# cs301_Team01_Schematic.net
KiCad netlist of a schematic drawn in Altium Designer
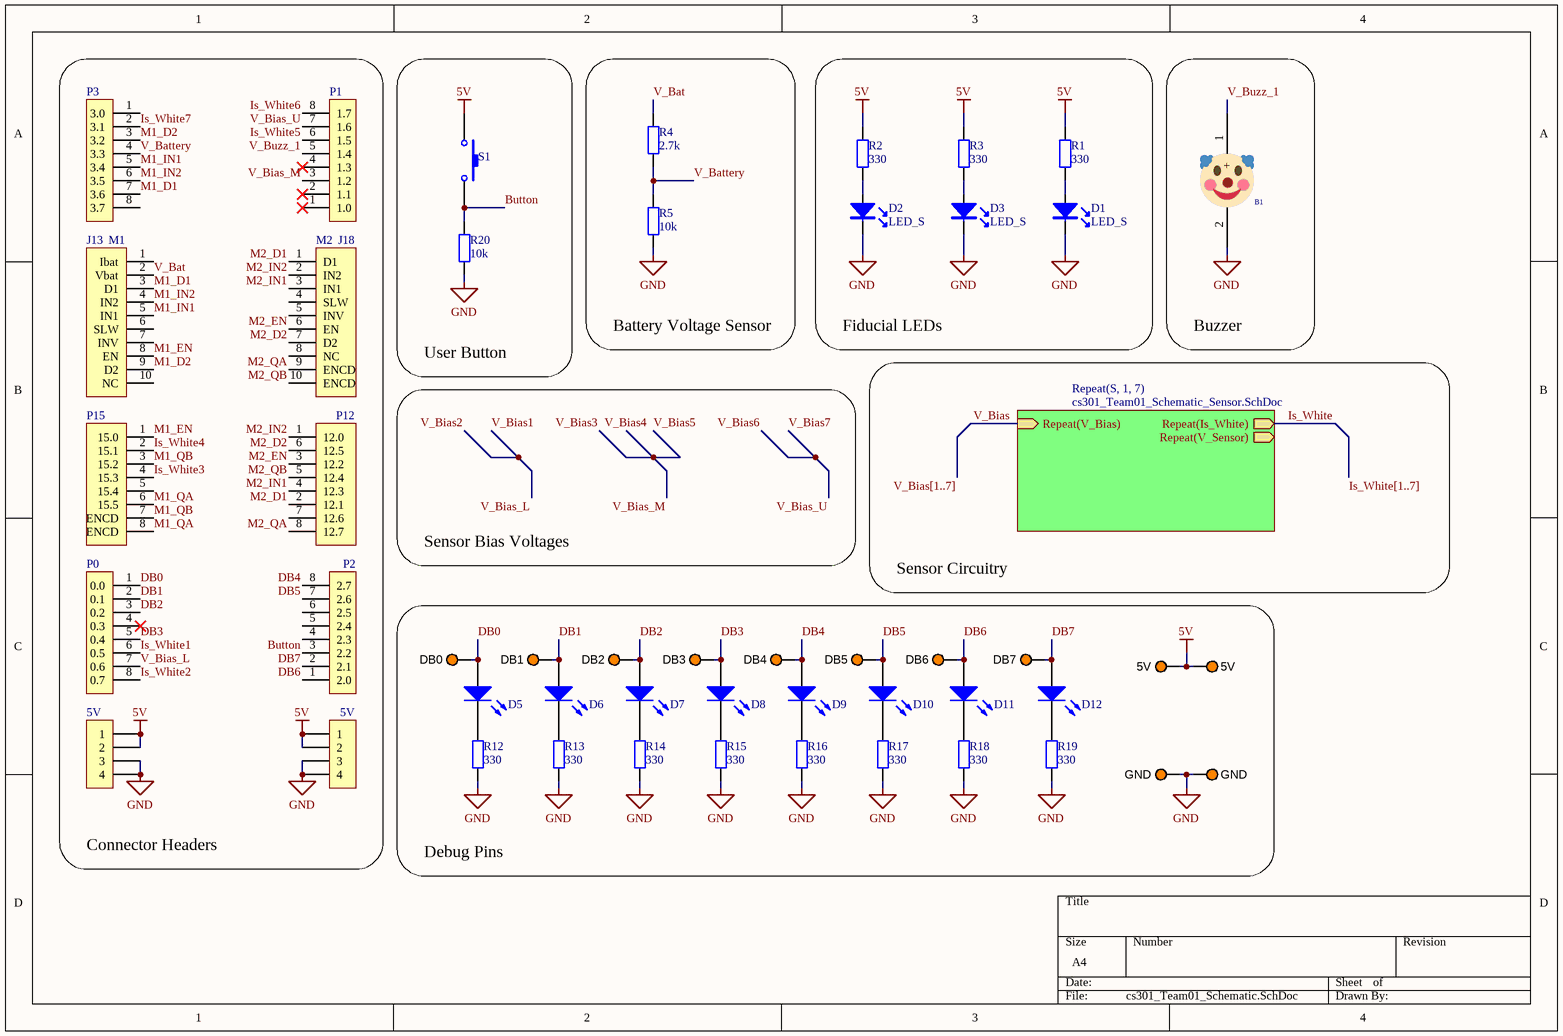
[diagram p0: cs301_Team01_Schematic.SchDoc]

(export (version "E")
  (design (tool "Eeschema 10.0.6"))
  (components
    (comp (ref "+5V")
      (value "5V")
      (footprint "IDC4")
      (description "Connector")
      (libsource (lib "Miscellaneous Devices") (part "CON4"))
    )
    (comp (ref "5V")
      (value "5V")
      (footprint "IDC4")
      (description "Connector")
      (libsource (lib "") (part "CON4_1"))
    )
    (comp (ref "5V_1")
      (value "5V")
      (footprint "TP_TH")
      (description "Test Point, Orange, 1-Pin THD, RoHS")
      (libsource (lib "EE209_Library") (part "TestPoint"))
    )
    (comp (ref "5V_2")
      (value "5V")
      (footprint "TP_TH")
      (description "Test Point, Orange, 1-Pin THD, RoHS")
      (libsource (lib "EE209_Library") (part "TestPoint"))
    )
    (comp (ref "B1") (value "clown") (footprint "Buzzer") (libsource (lib "buzzer") (part "Buzzer")))
    (comp (ref "D1") (value "LED_S") (footprint "LED0.1/5MM") (libsource (lib "COMSYS301_2013") (part "LED")))
    (comp (ref "D2") (value "LED_S") (footprint "LED0.1/5MM") (libsource (lib "COMSYS301_2013") (part "LED")))
    (comp (ref "D3") (value "LED_S") (footprint "LED0.1/5MM") (libsource (lib "COMSYS301_2013") (part "LED")))
    (comp (ref "D5")
      (value "0")
      (footprint "0805 LED")
      (description "SMT LED 0805 size")
      (fields
        (field (name "MANUFACTURER") "Lite-On Inc.")
        (field (name "MANUFACTURER PART NUMBER") "LTST-C170KGKT")
      )
      (libsource (lib "EE209_Library") (part "LED_SMT_0805"))
    )
    (comp (ref "D6")
      (value "1")
      (footprint "0805 LED")
      (description "SMT LED 0805 size")
      (fields
        (field (name "MANUFACTURER") "Lite-On Inc.")
        (field (name "MANUFACTURER PART NUMBER") "LTST-C170KGKT")
      )
      (libsource (lib "EE209_Library") (part "LED_SMT_0805"))
    )
    (comp (ref "D7")
      (value "2")
      (footprint "0805 LED")
      (description "SMT LED 0805 size")
      (fields
        (field (name "MANUFACTURER") "Lite-On Inc.")
        (field (name "MANUFACTURER PART NUMBER") "LTST-C170KGKT")
      )
      (libsource (lib "EE209_Library") (part "LED_SMT_0805"))
    )
    (comp (ref "D8")
      (value "3")
      (footprint "0805 LED")
      (description "SMT LED 0805 size")
      (fields
        (field (name "MANUFACTURER") "Lite-On Inc.")
        (field (name "MANUFACTURER PART NUMBER") "LTST-C170KGKT")
      )
      (libsource (lib "EE209_Library") (part "LED_SMT_0805"))
    )
    (comp (ref "D9")
      (value "4")
      (footprint "0805 LED")
      (description "SMT LED 0805 size")
      (fields
        (field (name "MANUFACTURER") "Lite-On Inc.")
        (field (name "MANUFACTURER PART NUMBER") "LTST-C170KGKT")
      )
      (libsource (lib "EE209_Library") (part "LED_SMT_0805"))
    )
    (comp (ref "D10")
      (value "5")
      (footprint "0805 LED")
      (description "SMT LED 0805 size")
      (fields
        (field (name "MANUFACTURER") "Lite-On Inc.")
        (field (name "MANUFACTURER PART NUMBER") "LTST-C170KGKT")
      )
      (libsource (lib "EE209_Library") (part "LED_SMT_0805"))
    )
    (comp (ref "D11")
      (value "6")
      (footprint "0805 LED")
      (description "SMT LED 0805 size")
      (fields
        (field (name "MANUFACTURER") "Lite-On Inc.")
        (field (name "MANUFACTURER PART NUMBER") "LTST-C170KGKT")
      )
      (libsource (lib "EE209_Library") (part "LED_SMT_0805"))
    )
    (comp (ref "D12")
      (value "7")
      (footprint "0805 LED")
      (description "SMT LED 0805 size")
      (fields
        (field (name "MANUFACTURER") "Lite-On Inc.")
        (field (name "MANUFACTURER PART NUMBER") "LTST-C170KGKT")
      )
      (libsource (lib "EE209_Library") (part "LED_SMT_0805"))
    )
    (comp (ref "DB0")
      (value "5003")
      (footprint "TP_TH")
      (description "Test Point, Orange, 1-Pin THD, RoHS")
      (libsource (lib "EE209_Library") (part "TestPoint"))
    )
    (comp (ref "DB1")
      (value "5003")
      (footprint "TP_TH")
      (description "Test Point, Orange, 1-Pin THD, RoHS")
      (libsource (lib "EE209_Library") (part "TestPoint"))
    )
    (comp (ref "DB2")
      (value "5003")
      (footprint "TP_TH")
      (description "Test Point, Orange, 1-Pin THD, RoHS")
      (libsource (lib "EE209_Library") (part "TestPoint"))
    )
    (comp (ref "DB3")
      (value "5003")
      (footprint "TP_TH")
      (description "Test Point, Orange, 1-Pin THD, RoHS")
      (libsource (lib "EE209_Library") (part "TestPoint"))
    )
    (comp (ref "DB4")
      (value "5003")
      (footprint "TP_TH")
      (description "Test Point, Orange, 1-Pin THD, RoHS")
      (libsource (lib "EE209_Library") (part "TestPoint"))
    )
    (comp (ref "DB5")
      (value "5003")
      (footprint "TP_TH")
      (description "Test Point, Orange, 1-Pin THD, RoHS")
      (libsource (lib "EE209_Library") (part "TestPoint"))
    )
    (comp (ref "DB6")
      (value "5003")
      (footprint "TP_TH")
      (description "Test Point, Orange, 1-Pin THD, RoHS")
      (libsource (lib "EE209_Library") (part "TestPoint"))
    )
    (comp (ref "DB7")
      (value "5003")
      (footprint "TP_TH")
      (description "Test Point, Orange, 1-Pin THD, RoHS")
      (libsource (lib "EE209_Library") (part "TestPoint"))
    )
    (comp (ref "GND_1")
      (value "GND")
      (footprint "TP_TH")
      (description "Test Point, Orange, 1-Pin THD, RoHS")
      (libsource (lib "EE209_Library") (part "TestPoint"))
    )
    (comp (ref "GND_2")
      (value "GND")
      (footprint "TP_TH")
      (description "Test Point, Orange, 1-Pin THD, RoHS")
      (libsource (lib "EE209_Library") (part "TestPoint"))
    )
    (comp (ref "J13")
      (value "M1")
      (footprint "idc10")
      (description "Connector")
      (libsource (lib "Miscellaneous Devices") (part "CON10"))
    )
    (comp (ref "J18")
      (value "M2")
      (footprint "IDC10")
      (description "Connector")
      (libsource (lib "") (part "CON10_1"))
    )
    (comp (ref "P0")
      (value "P0")
      (footprint "idc8")
      (description "Connector")
      (libsource (lib "") (part "CON8_2"))
    )
    (comp (ref "P1")
      (value "P1")
      (footprint "idc8")
      (description "Connector")
      (libsource (lib "Miscellaneous Devices") (part "CON8"))
    )
    (comp (ref "P2")
      (value "P2")
      (footprint "idc8")
      (description "Connector")
      (libsource (lib "") (part "CON8_1"))
    )
    (comp (ref "P3")
      (value "P3")
      (footprint "idc8")
      (description "Connector")
      (libsource (lib "") (part "CON8_2"))
    )
    (comp (ref "P12")
      (value "P12")
      (footprint "idc8")
      (description "Connector")
      (libsource (lib "") (part "CON8_1_1"))
    )
    (comp (ref "P15")
      (value "P15")
      (footprint "idc8")
      (description "Connector")
      (libsource (lib "Miscellaneous Devices") (part "CON8_1"))
    )
    (comp (ref "R1")
      (value "330")
      (footprint "0805 RES")
      (description "0805 resistor")
      (fields (field (name "PUBLISHER") "Altium Limited"))
      (libsource (lib "EE209_Library") (part "Res_SMT_0805"))
    )
    (comp (ref "R2")
      (value "330")
      (footprint "0805 RES")
      (description "0805 resistor")
      (fields (field (name "PUBLISHER") "Altium Limited"))
      (libsource (lib "EE209_Library") (part "Res_SMT_0805"))
    )
    (comp (ref "R3")
      (value "330")
      (footprint "0805 RES")
      (description "0805 resistor")
      (fields (field (name "PUBLISHER") "Altium Limited"))
      (libsource (lib "EE209_Library") (part "Res_SMT_0805"))
    )
    (comp (ref "R4")
      (value "2.7k")
      (footprint "0805 RES")
      (description "0805 resistor")
      (fields (field (name "PUBLISHER") "Altium Limited"))
      (libsource (lib "EE209_Library") (part "Res_SMT_0805"))
    )
    (comp (ref "R5")
      (value "10k")
      (footprint "0805 RES")
      (description "0805 resistor")
      (fields (field (name "PUBLISHER") "Altium Limited"))
      (libsource (lib "EE209_Library") (part "Res_SMT_0805"))
    )
    (comp (ref "R12")
      (value "330")
      (footprint "0805 RES")
      (description "0805 resistor")
      (fields (field (name "PUBLISHER") "Altium Limited"))
      (libsource (lib "EE209_Library") (part "Res_SMT_0805"))
    )
    (comp (ref "R13")
      (value "330")
      (footprint "0805 RES")
      (description "0805 resistor")
      (fields (field (name "PUBLISHER") "Altium Limited"))
      (libsource (lib "EE209_Library") (part "Res_SMT_0805"))
    )
    (comp (ref "R14")
      (value "330")
      (footprint "0805 RES")
      (description "0805 resistor")
      (fields (field (name "PUBLISHER") "Altium Limited"))
      (libsource (lib "EE209_Library") (part "Res_SMT_0805"))
    )
    (comp (ref "R15")
      (value "330")
      (footprint "0805 RES")
      (description "0805 resistor")
      (fields (field (name "PUBLISHER") "Altium Limited"))
      (libsource (lib "EE209_Library") (part "Res_SMT_0805"))
    )
    (comp (ref "R16")
      (value "330")
      (footprint "0805 RES")
      (description "0805 resistor")
      (fields (field (name "PUBLISHER") "Altium Limited"))
      (libsource (lib "EE209_Library") (part "Res_SMT_0805"))
    )
    (comp (ref "R17")
      (value "330")
      (footprint "0805 RES")
      (description "0805 resistor")
      (fields (field (name "PUBLISHER") "Altium Limited"))
      (libsource (lib "EE209_Library") (part "Res_SMT_0805"))
    )
    (comp (ref "R18")
      (value "330")
      (footprint "0805 RES")
      (description "0805 resistor")
      (fields (field (name "PUBLISHER") "Altium Limited"))
      (libsource (lib "EE209_Library") (part "Res_SMT_0805"))
    )
    (comp (ref "R19")
      (value "330")
      (footprint "0805 RES")
      (description "0805 resistor")
      (fields (field (name "PUBLISHER") "Altium Limited"))
      (libsource (lib "EE209_Library") (part "Res_SMT_0805"))
    )
    (comp (ref "R20")
      (value "10k")
      (footprint "0805 RES")
      (description "0805 resistor")
      (fields (field (name "PUBLISHER") "Altium Limited"))
      (libsource (lib "EE209_Library") (part "Res_SMT_0805"))
    )
    (comp (ref "S1")
      (value "PB switchTH_small")
      (footprint "ece-Sw-small")
      (description "Push Button Switch thru hole")
      (libsource (lib "ece components") (part "PB switchTH_small"))
    )
  )
  (nets
    (net (code "1") (name "/Button") (class "Default")
      (node (ref "P2") (pin "3") (pinfunction "2.2_3") (pintype "passive"))
      (node (ref "R20") (pin "2") (pinfunction "2_2") (pintype "passive"))
      (node (ref "S1") (pin "2") (pinfunction "2_2") (pintype "passive"))
    )
    (net (code "2") (name "/DB0") (class "Default")
      (node (ref "D5") (pin "1") (pinfunction "A_1") (pintype "passive"))
      (node (ref "DB0") (pin "1") (pinfunction "1_1") (pintype "passive"))
      (node (ref "P0") (pin "1") (pinfunction "3.0_1") (pintype "passive"))
    )
    (net (code "3") (name "/DB1") (class "Default")
      (node (ref "D6") (pin "1") (pinfunction "A_1") (pintype "passive"))
      (node (ref "DB1") (pin "1") (pinfunction "1_1") (pintype "passive"))
      (node (ref "P0") (pin "2") (pinfunction "3.1_2") (pintype "passive"))
    )
    (net (code "4") (name "/DB2") (class "Default")
      (node (ref "D7") (pin "1") (pinfunction "A_1") (pintype "passive"))
      (node (ref "DB2") (pin "1") (pinfunction "1_1") (pintype "passive"))
      (node (ref "P0") (pin "3") (pinfunction "3.2_3") (pintype "passive"))
    )
    (net (code "5") (name "/DB3") (class "Default")
      (node (ref "D8") (pin "1") (pinfunction "A_1") (pintype "passive"))
      (node (ref "DB3") (pin "1") (pinfunction "1_1") (pintype "passive"))
      (node (ref "P0") (pin "5") (pinfunction "3.4_5") (pintype "passive"))
    )
    (net (code "6") (name "/DB4") (class "Default")
      (node (ref "D9") (pin "1") (pinfunction "A_1") (pintype "passive"))
      (node (ref "DB4") (pin "1") (pinfunction "1_1") (pintype "passive"))
      (node (ref "P2") (pin "8") (pinfunction "2.7_8") (pintype "passive"))
    )
    (net (code "7") (name "/DB5") (class "Default")
      (node (ref "D10") (pin "1") (pinfunction "A_1") (pintype "passive"))
      (node (ref "DB5") (pin "1") (pinfunction "1_1") (pintype "passive"))
      (node (ref "P2") (pin "7") (pinfunction "2.6_7") (pintype "passive"))
    )
    (net (code "8") (name "/DB6") (class "Default")
      (node (ref "D11") (pin "1") (pinfunction "A_1") (pintype "passive"))
      (node (ref "DB6") (pin "1") (pinfunction "1_1") (pintype "passive"))
      (node (ref "P2") (pin "1") (pinfunction "2.0_1") (pintype "passive"))
    )
    (net (code "9") (name "/DB7") (class "Default")
      (node (ref "D12") (pin "1") (pinfunction "A_1") (pintype "passive"))
      (node (ref "DB7") (pin "1") (pinfunction "1_1") (pintype "passive"))
      (node (ref "P2") (pin "2") (pinfunction "2.1_2") (pintype "passive"))
    )
    (net (code "11") (name "/Is_White1") (class "Default")
      (node (ref "P0") (pin "6") (pinfunction "3.5_6") (pintype "passive"))
    )
    (net (code "12") (name "/Is_White2") (class "Default")
      (node (ref "P0") (pin "8") (pinfunction "3.7_8") (pintype "passive"))
    )
    (net (code "13") (name "/Is_White3") (class "Default")
      (node (ref "P15") (pin "4") (pinfunction "15.3_4") (pintype "passive"))
    )
    (net (code "14") (name "/Is_White4") (class "Default")
      (node (ref "P15") (pin "2") (pinfunction "15.1_2") (pintype "passive"))
    )
    (net (code "15") (name "/Is_White5") (class "Default")
      (node (ref "P1") (pin "6") (pinfunction "1.5_6") (pintype "passive"))
    )
    (net (code "16") (name "/Is_White6") (class "Default")
      (node (ref "P1") (pin "8") (pinfunction "1.7_8") (pintype "passive"))
    )
    (net (code "17") (name "/Is_White7") (class "Default")
      (node (ref "P3") (pin "2") (pinfunction "3.1_2") (pintype "passive"))
    )
    (net (code "19") (name "/M1_D1") (class "Default")
      (node (ref "J13") (pin "3") (pinfunction "D1_3") (pintype "passive"))
      (node (ref "P3") (pin "7") (pinfunction "3.6_7") (pintype "passive"))
    )
    (net (code "20") (name "/M1_D2") (class "Default")
      (node (ref "J13") (pin "9") (pinfunction "D2_9") (pintype "passive"))
      (node (ref "P3") (pin "3") (pinfunction "3.2_3") (pintype "passive"))
    )
    (net (code "21") (name "/M1_EN") (class "Default")
      (node (ref "J13") (pin "8") (pinfunction "EN_8") (pintype "passive"))
      (node (ref "P15") (pin "1") (pinfunction "15.0_1") (pintype "passive"))
    )
    (net (code "22") (name "/M1_IN1") (class "Default")
      (node (ref "J13") (pin "5") (pinfunction "IN1_5") (pintype "passive"))
      (node (ref "P3") (pin "5") (pinfunction "3.4_5") (pintype "passive"))
    )
    (net (code "23") (name "/M1_IN2") (class "Default")
      (node (ref "J13") (pin "4") (pinfunction "IN2_4") (pintype "passive"))
      (node (ref "P3") (pin "6") (pinfunction "3.5_6") (pintype "passive"))
    )
    (net (code "24") (name "/M1_QA") (class "Default")
      (node (ref "P15") (pin "6") (pinfunction "15.5_6") (pintype "passive"))
      (node (ref "P15") (pin "8") (pinfunction "ENCD_8") (pintype "passive"))
    )
    (net (code "25") (name "/M1_QB") (class "Default")
      (node (ref "P15") (pin "3") (pinfunction "15.2_3") (pintype "passive"))
      (node (ref "P15") (pin "7") (pinfunction "ENCD_7") (pintype "passive"))
    )
    (net (code "26") (name "/M2_D1") (class "Default")
      (node (ref "J18") (pin "1") (pinfunction "D1_1") (pintype "passive"))
      (node (ref "P12") (pin "2") (pinfunction "12.1_2") (pintype "passive"))
    )
    (net (code "27") (name "/M2_D2") (class "Default")
      (node (ref "J18") (pin "7") (pinfunction "D2_7") (pintype "passive"))
      (node (ref "P12") (pin "6") (pinfunction "12.5_6") (pintype "passive"))
    )
    (net (code "28") (name "/M2_EN") (class "Default")
      (node (ref "J18") (pin "6") (pinfunction "EN_6") (pintype "passive"))
      (node (ref "P12") (pin "3") (pinfunction "12.2_3") (pintype "passive"))
    )
    (net (code "29") (name "/M2_IN1") (class "Default")
      (node (ref "J18") (pin "3") (pinfunction "IN1_3") (pintype "passive"))
      (node (ref "P12") (pin "4") (pinfunction "12.3_4") (pintype "passive"))
    )
    (net (code "30") (name "/M2_IN2") (class "Default")
      (node (ref "J18") (pin "2") (pinfunction "IN2_2") (pintype "passive"))
      (node (ref "P12") (pin "1") (pinfunction "12.0_1") (pintype "passive"))
    )
    (net (code "31") (name "/M2_QA") (class "Default")
      (node (ref "J18") (pin "9") (pinfunction "ENCD_9") (pintype "passive"))
      (node (ref "P12") (pin "8") (pinfunction "12.7_8") (pintype "passive"))
    )
    (net (code "32") (name "/M2_QB") (class "Default")
      (node (ref "J18") (pin "10") (pinfunction "ENCD_10") (pintype "passive"))
      (node (ref "P12") (pin "5") (pinfunction "12.4_5") (pintype "passive"))
    )
    (net (code "34") (name "/V_Bat") (class "Default")
      (node (ref "J13") (pin "2") (pinfunction "Vbat_2") (pintype "passive"))
      (node (ref "R4") (pin "2") (pinfunction "2_2") (pintype "passive"))
    )
    (net (code "35") (name "/V_Battery") (class "Default")
      (node (ref "P3") (pin "4") (pinfunction "3.3_4") (pintype "passive"))
      (node (ref "R4") (pin "1") (pinfunction "1_1") (pintype "passive"))
      (node (ref "R5") (pin "2") (pinfunction "2_2") (pintype "passive"))
    )
    (net (code "37") (name "/V_Bias2") (class "Default")
      (node (ref "P0") (pin "7") (pinfunction "3.6_7") (pintype "passive"))
    )
    (net (code "38") (name "/V_Bias5") (class "Default")
      (node (ref "P1") (pin "3") (pinfunction "1.2_3") (pintype "passive"))
    )
    (net (code "39") (name "/V_Bias7") (class "Default")
      (node (ref "P1") (pin "7") (pinfunction "1.6_7") (pintype "passive"))
    )
    (net (code "41") (name "/V_Buzz_1") (class "Default")
      (node (ref "B1") (pin "1") (pinfunction "+_1") (pintype "passive"))
      (node (ref "P1") (pin "5") (pinfunction "1.4_5") (pintype "passive"))
    )
    (net (code "42") (name "5V") (class "Default")
      (node (ref "+5V") (pin "1") (pinfunction "1_1") (pintype "passive"))
      (node (ref "+5V") (pin "2") (pinfunction "2_2") (pintype "passive"))
      (node (ref "5V") (pin "1") (pinfunction "1_1") (pintype "passive"))
      (node (ref "5V") (pin "2") (pinfunction "2_2") (pintype "passive"))
      (node (ref "5V_1") (pin "1") (pinfunction "1_1") (pintype "passive"))
      (node (ref "5V_2") (pin "1") (pinfunction "1_1") (pintype "passive"))
      (node (ref "R1") (pin "2") (pinfunction "2_2") (pintype "passive"))
      (node (ref "R2") (pin "2") (pinfunction "2_2") (pintype "passive"))
      (node (ref "R3") (pin "2") (pinfunction "2_2") (pintype "passive"))
      (node (ref "S1") (pin "1") (pinfunction "1_1") (pintype "passive"))
    )
    (net (code "43") (name "GND") (class "Default")
      (node (ref "+5V") (pin "3") (pinfunction "3_3") (pintype "passive"))
      (node (ref "+5V") (pin "4") (pinfunction "4_4") (pintype "passive"))
      (node (ref "5V") (pin "3") (pinfunction "3_3") (pintype "passive"))
      (node (ref "5V") (pin "4") (pinfunction "4_4") (pintype "passive"))
      (node (ref "B1") (pin "2") (pinfunction "-_2") (pintype "passive"))
      (node (ref "D1") (pin "K") (pinfunction "2_K") (pintype "passive"))
      (node (ref "D2") (pin "K") (pinfunction "2_K") (pintype "passive"))
      (node (ref "D3") (pin "K") (pinfunction "2_K") (pintype "passive"))
      (node (ref "GND_1") (pin "1") (pinfunction "1_1") (pintype "passive"))
      (node (ref "GND_2") (pin "1") (pinfunction "1_1") (pintype "passive"))
      (node (ref "R12") (pin "1") (pinfunction "1_1") (pintype "passive"))
      (node (ref "R13") (pin "1") (pinfunction "1_1") (pintype "passive"))
      (node (ref "R14") (pin "1") (pinfunction "1_1") (pintype "passive"))
      (node (ref "R15") (pin "1") (pinfunction "1_1") (pintype "passive"))
      (node (ref "R16") (pin "1") (pinfunction "1_1") (pintype "passive"))
      (node (ref "R17") (pin "1") (pinfunction "1_1") (pintype "passive"))
      (node (ref "R18") (pin "1") (pinfunction "1_1") (pintype "passive"))
      (node (ref "R19") (pin "1") (pinfunction "1_1") (pintype "passive"))
      (node (ref "R20") (pin "1") (pinfunction "1_1") (pintype "passive"))
      (node (ref "R5") (pin "1") (pinfunction "1_1") (pintype "passive"))
    )
    (net (code "44") (name "Net-(D1-1)") (class "Default")
      (node (ref "D1") (pin "A") (pinfunction "1_A") (pintype "passive"))
      (node (ref "R1") (pin "1") (pinfunction "1_1") (pintype "passive"))
    )
    (net (code "45") (name "Net-(D2-1)") (class "Default")
      (node (ref "D2") (pin "A") (pinfunction "1_A") (pintype "passive"))
      (node (ref "R2") (pin "1") (pinfunction "1_1") (pintype "passive"))
    )
    (net (code "46") (name "Net-(D3-1)") (class "Default")
      (node (ref "D3") (pin "A") (pinfunction "1_A") (pintype "passive"))
      (node (ref "R3") (pin "1") (pinfunction "1_1") (pintype "passive"))
    )
    (net (code "47") (name "Net-(D5-K)") (class "Default")
      (node (ref "D5") (pin "2") (pinfunction "K_2") (pintype "passive"))
      (node (ref "R12") (pin "2") (pinfunction "2_2") (pintype "passive"))
    )
    (net (code "48") (name "Net-(D6-K)") (class "Default")
      (node (ref "D6") (pin "2") (pinfunction "K_2") (pintype "passive"))
      (node (ref "R13") (pin "2") (pinfunction "2_2") (pintype "passive"))
    )
    (net (code "49") (name "Net-(D7-K)") (class "Default")
      (node (ref "D7") (pin "2") (pinfunction "K_2") (pintype "passive"))
      (node (ref "R14") (pin "2") (pinfunction "2_2") (pintype "passive"))
    )
    (net (code "50") (name "Net-(D8-K)") (class "Default")
      (node (ref "D8") (pin "2") (pinfunction "K_2") (pintype "passive"))
      (node (ref "R15") (pin "2") (pinfunction "2_2") (pintype "passive"))
    )
    (net (code "51") (name "Net-(D9-K)") (class "Default")
      (node (ref "D9") (pin "2") (pinfunction "K_2") (pintype "passive"))
      (node (ref "R16") (pin "2") (pinfunction "2_2") (pintype "passive"))
    )
    (net (code "52") (name "Net-(D10-K)") (class "Default")
      (node (ref "D10") (pin "2") (pinfunction "K_2") (pintype "passive"))
      (node (ref "R17") (pin "2") (pinfunction "2_2") (pintype "passive"))
    )
    (net (code "53") (name "Net-(D11-K)") (class "Default")
      (node (ref "D11") (pin "2") (pinfunction "K_2") (pintype "passive"))
      (node (ref "R18") (pin "2") (pinfunction "2_2") (pintype "passive"))
    )
    (net (code "54") (name "Net-(D12-K)") (class "Default")
      (node (ref "D12") (pin "2") (pinfunction "K_2") (pintype "passive"))
      (node (ref "R19") (pin "2") (pinfunction "2_2") (pintype "passive"))
    )
    (net (code "55") (name "unconnected-(J13-INV-Pad7)") (class "Default")
      (node (ref "J13") (pin "7") (pinfunction "INV_7") (pintype "passive"))
    )
    (net (code "56") (name "unconnected-(J13-Ibat-Pad1)") (class "Default")
      (node (ref "J13") (pin "1") (pinfunction "Ibat_1") (pintype "passive"))
    )
    (net (code "57") (name "unconnected-(J13-NC-Pad10)") (class "Default")
      (node (ref "J13") (pin "10") (pinfunction "NC_10") (pintype "passive"))
    )
    (net (code "58") (name "unconnected-(J13-SLW-Pad6)") (class "Default")
      (node (ref "J13") (pin "6") (pinfunction "SLW_6") (pintype "passive"))
    )
    (net (code "59") (name "unconnected-(J18-INV-Pad5)") (class "Default")
      (node (ref "J18") (pin "5") (pinfunction "INV_5") (pintype "passive"))
    )
    (net (code "60") (name "unconnected-(J18-NC-Pad8)") (class "Default")
      (node (ref "J18") (pin "8") (pinfunction "NC_8") (pintype "passive"))
    )
    (net (code "61") (name "unconnected-(J18-SLW-Pad4)") (class "Default")
      (node (ref "J18") (pin "4") (pinfunction "SLW_4") (pintype "passive"))
    )
    (net (code "62") (name "unconnected-(P0-3.3-Pad4)") (class "Default")
      (node (ref "P0") (pin "4") (pinfunction "3.3_4") (pintype "passive+no_connect"))
    )
    (net (code "63") (name "unconnected-(P1-1.0-Pad1)") (class "Default")
      (node (ref "P1") (pin "1") (pinfunction "1.0_1") (pintype "passive+no_connect"))
    )
    (net (code "64") (name "unconnected-(P1-1.1-Pad2)") (class "Default")
      (node (ref "P1") (pin "2") (pinfunction "1.1_2") (pintype "passive+no_connect"))
    )
    (net (code "65") (name "unconnected-(P1-1.3-Pad4)") (class "Default")
      (node (ref "P1") (pin "4") (pinfunction "1.3_4") (pintype "passive+no_connect"))
    )
    (net (code "66") (name "unconnected-(P2-2.3-Pad4)") (class "Default")
      (node (ref "P2") (pin "4") (pinfunction "2.3_4") (pintype "passive"))
    )
    (net (code "67") (name "unconnected-(P2-2.4-Pad5)") (class "Default")
      (node (ref "P2") (pin "5") (pinfunction "2.4_5") (pintype "passive"))
    )
    (net (code "68") (name "unconnected-(P2-2.5-Pad6)") (class "Default")
      (node (ref "P2") (pin "6") (pinfunction "2.5_6") (pintype "passive"))
    )
    (net (code "69") (name "unconnected-(P3-3.0-Pad1)") (class "Default")
      (node (ref "P3") (pin "1") (pinfunction "3.0_1") (pintype "passive"))
    )
    (net (code "70") (name "unconnected-(P3-3.7-Pad8)") (class "Default")
      (node (ref "P3") (pin "8") (pinfunction "3.7_8") (pintype "passive"))
    )
    (net (code "71") (name "unconnected-(P12-12.6-Pad7)") (class "Default")
      (node (ref "P12") (pin "7") (pinfunction "12.6_7") (pintype "passive"))
    )
    (net (code "72") (name "unconnected-(P15-15.4-Pad5)") (class "Default")
      (node (ref "P15") (pin "5") (pinfunction "15.4_5") (pintype "passive"))
    )
  )
)
